# amp.net
KiCad netlist of a schematic drawn in Altium Designer
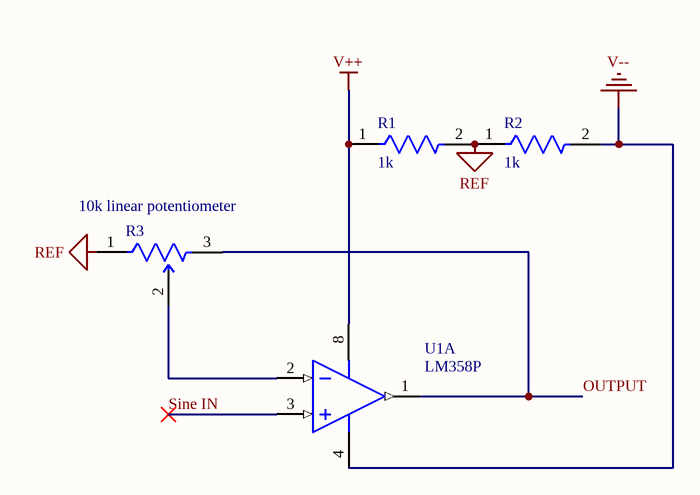
[diagram p0: amp.SchDoc]

(export (version "E")
  (design (tool "Eeschema 10.0.6"))
  (components
    (comp (ref "R1")
      (value "1k")
      (footprint "FP-MRS25-MFG")
      (description "RES 1K OHM 0.6W 1% AXIAL")
      (fields (field (name "TOLERANCE") "1%"))
      (libsource (lib "Altium Content Vault") (part "1029c3af85768c4190bb7ad29bc67b5"))
    )
    (comp (ref "R2")
      (value "1k")
      (footprint "FP-MRS25-MFG")
      (description "RES 1K OHM 0.6W 1% AXIAL")
      (fields (field (name "TOLERANCE") "1%"))
      (libsource (lib "Altium Content Vault") (part "1029c3af85768c4190bb7ad29bc67b5"))
    )
    (comp (ref "R3")
      (value "10k linear potentiometer")
      (footprint "FP-TS53YL-MFG")
      (description "TRIMMER 10K OHM 0.25W GW TOP ADJ")
      (fields (field (name "TOLERANCE") "20%"))
      (libsource (lib "Altium Content Vault") (part "af6d6fb613c1f66b9b47f3e4c9350cb"))
    )
    (comp (ref "U1")
      (value "LM358P")
      (footprint "P0008A")
      (description "Dual Operational Amplifier, 3 to 32 V, 0 to 70 degC, 8-Pin PDIP (P), RoHS, Tape and Reel")
      (fields (field (name "MANUFACTURER") "Technik Industrial"))
      (libsource (lib "Altium Content Vault") (part "TI-LM_LPXXX-SO_DIP8"))
    )
  )
  (nets
    (net (code "1") (name "/OUTPUT") (class "Default")
      (node (ref "R3") (pin "3") (pinfunction "c_3") (pintype "passive"))
      (node (ref "U1") (pin "1") (pinfunction "1OUT_1") (pintype "output"))
    )
    (net (code "2") (name "/Sine IN") (class "Default")
      (node (ref "U1") (pin "3") (pinfunction "1IN+_3") (pintype "input+no_connect"))
    )
    (net (code "3") (name "Net-(R3-b)") (class "Default")
      (node (ref "R3") (pin "2") (pinfunction "b_2") (pintype "passive"))
      (node (ref "U1") (pin "2") (pinfunction "1IN-_2") (pintype "input"))
    )
    (net (code "4") (name "REF") (class "Default")
      (node (ref "R1") (pin "2") (pinfunction "2_2") (pintype "passive"))
      (node (ref "R2") (pin "1") (pinfunction "1_1") (pintype "passive"))
      (node (ref "R3") (pin "1") (pinfunction "a_1") (pintype "passive"))
    )
    (net (code "5") (name "V++") (class "Default")
      (node (ref "R1") (pin "1") (pinfunction "1_1") (pintype "passive"))
      (node (ref "U1") (pin "8") (pinfunction "VCC_8") (pintype "power_in"))
    )
    (net (code "6") (name "V--") (class "Default")
      (node (ref "R2") (pin "2") (pinfunction "2_2") (pintype "passive"))
      (node (ref "U1") (pin "4") (pinfunction "GND_4") (pintype "power_in"))
    )
  )
)
